# FabScan-Shield_v10.net
KiCad netlist of a schematic drawn in EAGLE
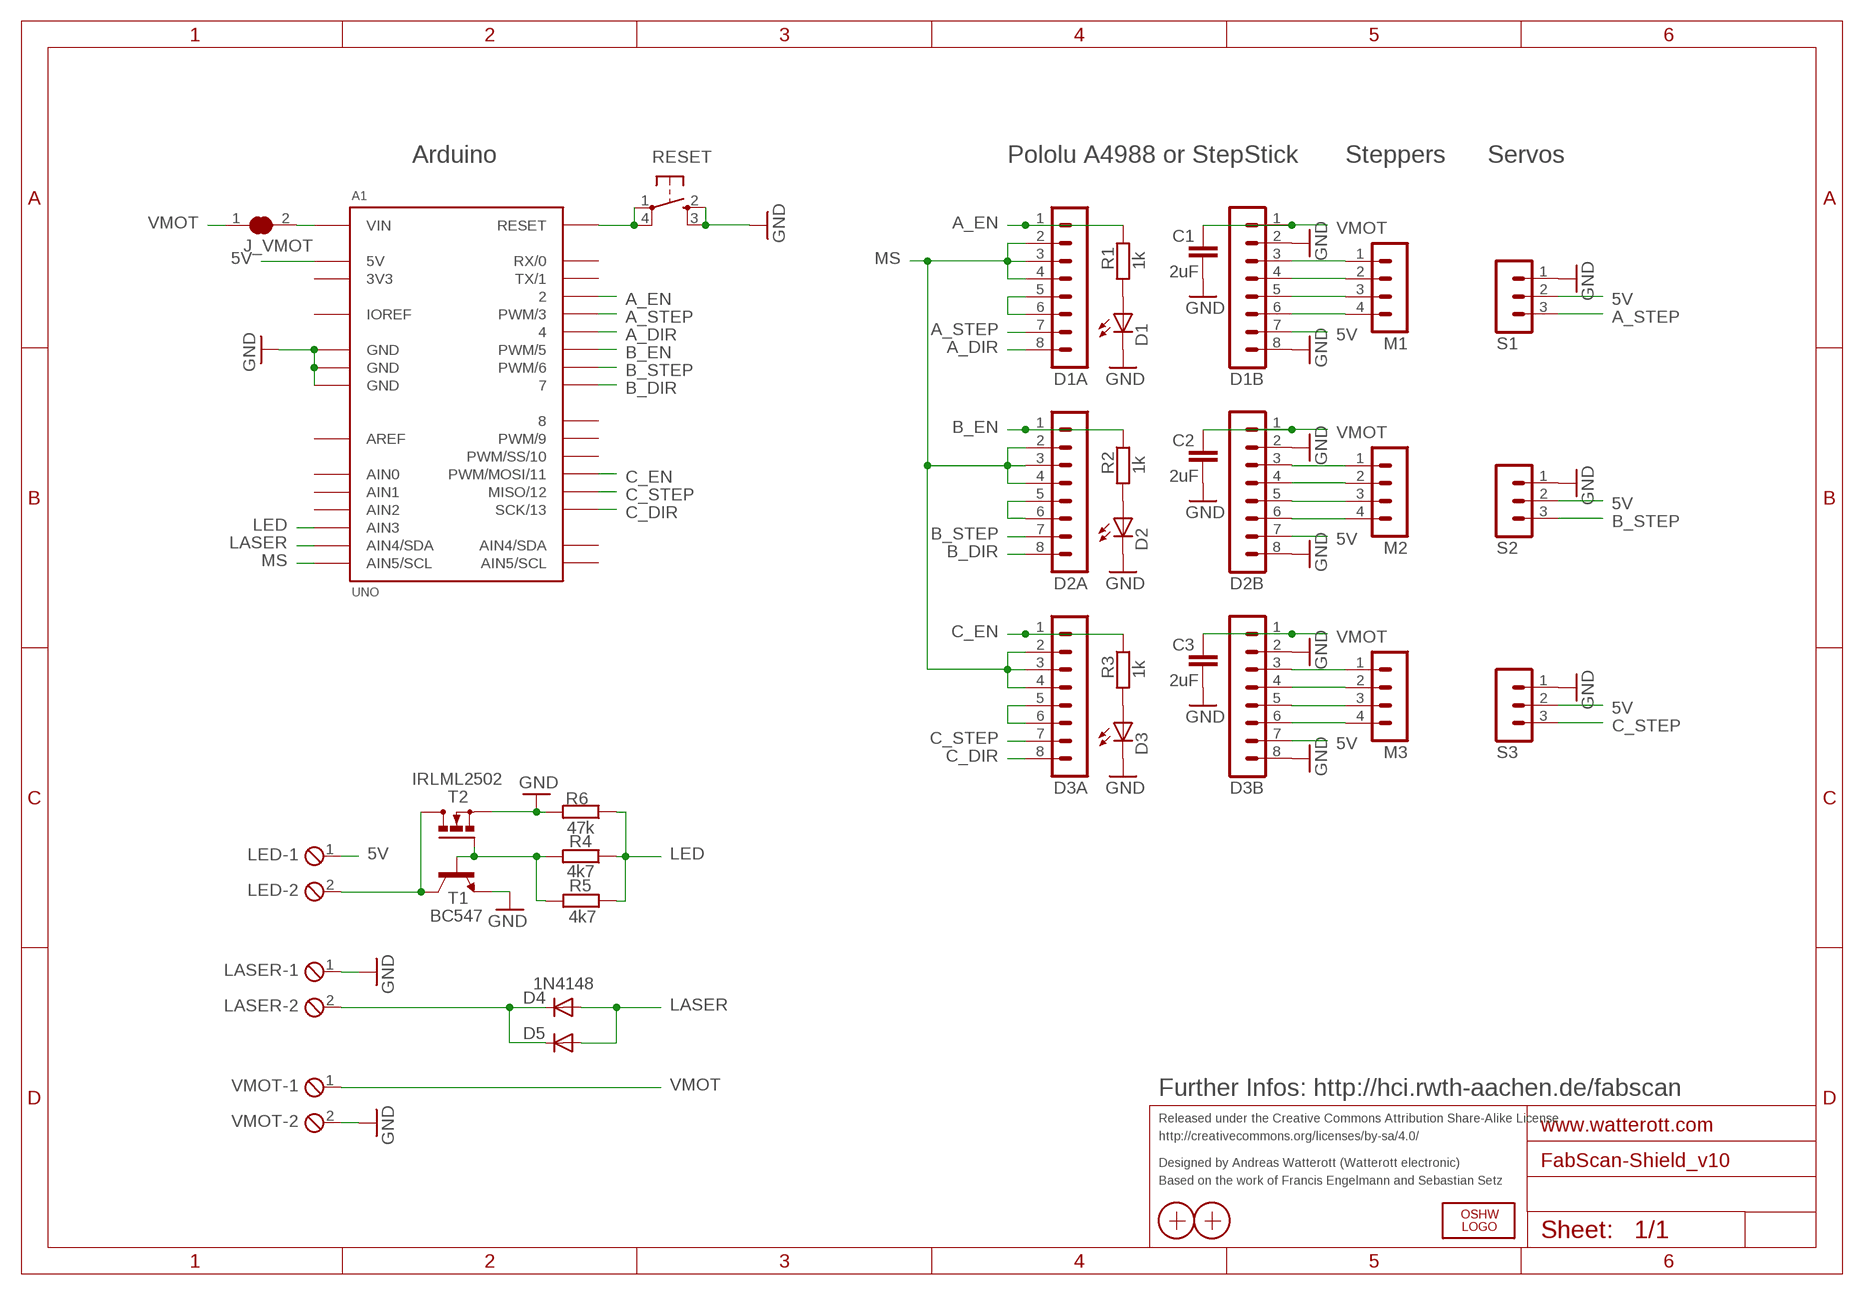
[diagram p0: schematic, sheet 1]

(export (version "E")
  (design (tool "Eeschema 10.0.6"))
  (components
    (comp (ref "A1")
      (value "UNO")
      (footprint "eagle-import:UNO")
      (libsource (lib "eagle-import") (part "UNO"))
    )
    (comp (ref "C1")
      (value "2uF")
      (footprint "eagle-import:C0603")
      (libsource (lib "eagle-import") (part "C-EUC0603"))
    )
    (comp (ref "C2")
      (value "2uF")
      (footprint "eagle-import:C0603")
      (libsource (lib "eagle-import") (part "C-EUC0603"))
    )
    (comp (ref "C3")
      (value "2uF")
      (footprint "eagle-import:C0603")
      (libsource (lib "eagle-import") (part "C-EUC0603"))
    )
    (comp (ref "D1")
      (value "LEDCHIPLED_0603")
      (footprint "eagle-import:CHIPLED_0603")
      (libsource (lib "eagle-import") (part "LEDCHIPLED_0603"))
    )
    (comp (ref "D1A")
      (value "MA08-1")
      (footprint "eagle-import:MA08-1")
      (libsource (lib "eagle-import") (part "MA08-1"))
    )
    (comp (ref "D1B")
      (value "MA08-1")
      (footprint "eagle-import:MA08-1")
      (libsource (lib "eagle-import") (part "MA08-1"))
    )
    (comp (ref "D2")
      (value "LEDCHIPLED_0603")
      (footprint "eagle-import:CHIPLED_0603")
      (libsource (lib "eagle-import") (part "LEDCHIPLED_0603"))
    )
    (comp (ref "D2A")
      (value "MA08-1")
      (footprint "eagle-import:MA08-1")
      (libsource (lib "eagle-import") (part "MA08-1"))
    )
    (comp (ref "D2B")
      (value "MA08-1")
      (footprint "eagle-import:MA08-1")
      (libsource (lib "eagle-import") (part "MA08-1"))
    )
    (comp (ref "D3")
      (value "LEDCHIPLED_0603")
      (footprint "eagle-import:CHIPLED_0603")
      (libsource (lib "eagle-import") (part "LEDCHIPLED_0603"))
    )
    (comp (ref "D3A")
      (value "MA08-1")
      (footprint "eagle-import:MA08-1")
      (libsource (lib "eagle-import") (part "MA08-1"))
    )
    (comp (ref "D3B")
      (value "MA08-1")
      (footprint "eagle-import:MA08-1")
      (libsource (lib "eagle-import") (part "MA08-1"))
    )
    (comp (ref "D4")
      (value "1N4148")
      (footprint "eagle-import:DO35-7")
      (libsource (lib "eagle-import") (part "1N4148DO35-7"))
    )
    (comp (ref "D5")
      (value "DIODE-SOD106-R")
      (footprint "eagle-import:SOD106-R")
      (libsource (lib "eagle-import") (part "DIODE-SOD106-R"))
    )
    (comp (ref "J_VMOT")
      (value "SJ")
      (footprint "eagle-import:SJ")
      (libsource (lib "eagle-import") (part "SJ"))
    )
    (comp (ref "LASER")
      (value "MPT2")
      (footprint "eagle-import:2POL254")
      (fields (field (name "OC_FARNELL") "unknown") (field (name "OC_NEWARK") "unknown"))
      (libsource (lib "eagle-import") (part "MPT2"))
    )
    (comp (ref "LED")
      (value "MPT2")
      (footprint "eagle-import:2POL254")
      (libsource (lib "eagle-import") (part "MPT2"))
    )
    (comp (ref "LOGO2")
      (value "OSHW_LOGO_6MILX0100-NT")
      (footprint "eagle-import:OSHW_6X100_NOTEXT")
      (libsource (lib "eagle-import") (part "OSHW_LOGO_6MILX0100-NT"))
    )
    (comp (ref "M1")
      (value "MA04-1")
      (footprint "eagle-import:MA04-1")
      (libsource (lib "eagle-import") (part "MA04-1"))
    )
    (comp (ref "M2")
      (value "MA04-1")
      (footprint "eagle-import:MA04-1")
      (fields (field (name "OC_FARNELL") "unknown") (field (name "OC_NEWARK") "unknown"))
      (libsource (lib "eagle-import") (part "MA04-1"))
    )
    (comp (ref "M3")
      (value "MA04-1")
      (footprint "eagle-import:MA04-1")
      (fields (field (name "OC_FARNELL") "unknown") (field (name "OC_NEWARK") "unknown"))
      (libsource (lib "eagle-import") (part "MA04-1"))
    )
    (comp (ref "R1")
      (value "1k")
      (footprint "eagle-import:R0603")
      (libsource (lib "eagle-import") (part "R-EU_R0603"))
    )
    (comp (ref "R2")
      (value "1k")
      (footprint "eagle-import:R0603")
      (libsource (lib "eagle-import") (part "R-EU_R0603"))
    )
    (comp (ref "R3")
      (value "1k")
      (footprint "eagle-import:R0603")
      (libsource (lib "eagle-import") (part "R-EU_R0603"))
    )
    (comp (ref "R4")
      (value "4k7")
      (footprint "eagle-import:0204_7")
      (libsource (lib "eagle-import") (part "R-EU_0204/7"))
    )
    (comp (ref "R5")
      (value "4k7")
      (footprint "eagle-import:R0603")
      (libsource (lib "eagle-import") (part "R-EU_R0603"))
    )
    (comp (ref "R6")
      (value "47k")
      (footprint "eagle-import:R0603")
      (libsource (lib "eagle-import") (part "R-EU_R0603"))
    )
    (comp (ref "RESET")
      (value "SW_SMDS")
      (footprint "eagle-import:SW_SMD4")
      (libsource (lib "eagle-import") (part "SW_SMDS"))
    )
    (comp (ref "S1")
      (value "MA03-1")
      (footprint "eagle-import:MA03-1")
      (libsource (lib "eagle-import") (part "MA03-1"))
    )
    (comp (ref "S2")
      (value "MA03-1")
      (footprint "eagle-import:MA03-1")
      (libsource (lib "eagle-import") (part "MA03-1"))
    )
    (comp (ref "S3")
      (value "MA03-1")
      (footprint "eagle-import:MA03-1")
      (libsource (lib "eagle-import") (part "MA03-1"))
    )
    (comp (ref "T1")
      (value "BC547")
      (footprint "eagle-import:TO92")
      (libsource (lib "eagle-import") (part "BC547"))
    )
    (comp (ref "T2")
      (value "IRLML2502")
      (footprint "eagle-import:MICRO3")
      (libsource (lib "eagle-import") (part "IRLML2502"))
    )
    (comp (ref "VMOT")
      (value "MPT2")
      (footprint "eagle-import:2POL254")
      (fields (field (name "OC_FARNELL") "unknown") (field (name "OC_NEWARK") "unknown"))
      (libsource (lib "eagle-import") (part "MPT2"))
    )
    (comp (ref "X1")
      (value "PASSER")
      (footprint "eagle-import:PASSER")
      (libsource (lib "eagle-import") (part "PASSER"))
    )
    (comp (ref "X2")
      (value "PASSER")
      (footprint "eagle-import:PASSER")
      (libsource (lib "eagle-import") (part "PASSER"))
    )
  )
  (nets
    (net (code "1") (name "/3V3") (class "Default")
      (node (ref "A1") (pin "3V3") (pinfunction "3V3_3V3") (pintype "power_in"))
    )
    (net (code "2") (name "/5V") (class "Default")
      (node (ref "A1") (pin "5V") (pinfunction "5V_5V") (pintype "power_in"))
      (node (ref "D1B") (pin "7") (pinfunction "7_7") (pintype "passive"))
      (node (ref "D2B") (pin "7") (pinfunction "7_7") (pintype "passive"))
      (node (ref "D3B") (pin "7") (pinfunction "7_7") (pintype "passive"))
      (node (ref "LED") (pin "1") (pinfunction "1_1") (pintype "passive"))
      (node (ref "S1") (pin "2") (pinfunction "2_2") (pintype "passive"))
      (node (ref "S2") (pin "2") (pinfunction "2_2") (pintype "passive"))
      (node (ref "S3") (pin "2") (pinfunction "2_2") (pintype "passive"))
    )
    (net (code "3") (name "/AREF") (class "Default")
      (node (ref "A1") (pin "AREF") (pinfunction "AREF_AREF") (pintype "power_in"))
    )
    (net (code "4") (name "/A_DIR") (class "Default")
      (node (ref "A1") (pin "4") (pinfunction "4_4") (pintype "bidirectional"))
      (node (ref "D1A") (pin "8") (pinfunction "8_8") (pintype "passive"))
    )
    (net (code "5") (name "/A_EN") (class "Default")
      (node (ref "A1") (pin "2") (pinfunction "2_2") (pintype "bidirectional"))
      (node (ref "D1A") (pin "1") (pinfunction "1_1") (pintype "passive"))
      (node (ref "R1") (pin "1") (pinfunction "1_1") (pintype "passive"))
    )
    (net (code "6") (name "/A_STEP") (class "Default")
      (node (ref "A1") (pin "3") (pinfunction "PWM/3_3") (pintype "bidirectional"))
      (node (ref "D1A") (pin "7") (pinfunction "7_7") (pintype "passive"))
      (node (ref "S1") (pin "3") (pinfunction "3_3") (pintype "passive"))
    )
    (net (code "7") (name "/B_DIR") (class "Default")
      (node (ref "A1") (pin "7") (pinfunction "7_7") (pintype "bidirectional"))
      (node (ref "D2A") (pin "8") (pinfunction "8_8") (pintype "passive"))
    )
    (net (code "8") (name "/B_EN") (class "Default")
      (node (ref "A1") (pin "5") (pinfunction "PWM/5_5") (pintype "bidirectional"))
      (node (ref "D2A") (pin "1") (pinfunction "1_1") (pintype "passive"))
      (node (ref "R2") (pin "1") (pinfunction "1_1") (pintype "passive"))
    )
    (net (code "9") (name "/B_STEP") (class "Default")
      (node (ref "A1") (pin "6") (pinfunction "PWM/6_6") (pintype "bidirectional"))
      (node (ref "D2A") (pin "7") (pinfunction "7_7") (pintype "passive"))
      (node (ref "S2") (pin "3") (pinfunction "3_3") (pintype "passive"))
    )
    (net (code "10") (name "/C_DIR") (class "Default")
      (node (ref "A1") (pin "13") (pinfunction "SCK/13_13") (pintype "bidirectional"))
      (node (ref "D3A") (pin "8") (pinfunction "8_8") (pintype "passive"))
    )
    (net (code "11") (name "/C_EN") (class "Default")
      (node (ref "A1") (pin "11") (pinfunction "PWM/MOSI/11_11") (pintype "bidirectional"))
      (node (ref "D3A") (pin "1") (pinfunction "1_1") (pintype "passive"))
      (node (ref "R3") (pin "1") (pinfunction "1_1") (pintype "passive"))
    )
    (net (code "12") (name "/C_STEP") (class "Default")
      (node (ref "A1") (pin "12") (pinfunction "MISO/12_12") (pintype "bidirectional"))
      (node (ref "D3A") (pin "7") (pinfunction "7_7") (pintype "passive"))
      (node (ref "S3") (pin "3") (pinfunction "3_3") (pintype "passive"))
    )
    (net (code "13") (name "/IOREF") (class "Default")
      (node (ref "A1") (pin "IOREF") (pinfunction "IOREF_IOREF") (pintype "power_in"))
    )
    (net (code "14") (name "/LASER") (class "Default")
      (node (ref "A1") (pin "AIN4") (pinfunction "AIN4/SDA_AIN4") (pintype "bidirectional"))
      (node (ref "D4") (pin "A") (pinfunction "A_A") (pintype "passive"))
      (node (ref "D5") (pin "A") (pinfunction "A_A") (pintype "passive"))
    )
    (net (code "15") (name "/LED") (class "Default")
      (node (ref "A1") (pin "AIN3") (pinfunction "AIN3_AIN3") (pintype "bidirectional"))
      (node (ref "R4") (pin "1") (pinfunction "1_1") (pintype "passive"))
      (node (ref "R5") (pin "2") (pinfunction "2_2") (pintype "passive"))
      (node (ref "R6") (pin "1") (pinfunction "1_1") (pintype "passive"))
    )
    (net (code "16") (name "/MS") (class "Default")
      (node (ref "A1") (pin "AIN5") (pinfunction "AIN5/SCL_AIN5") (pintype "bidirectional"))
      (node (ref "D1A") (pin "2") (pinfunction "2_2") (pintype "passive"))
      (node (ref "D1A") (pin "3") (pinfunction "3_3") (pintype "passive"))
      (node (ref "D1A") (pin "4") (pinfunction "4_4") (pintype "passive"))
      (node (ref "D2A") (pin "2") (pinfunction "2_2") (pintype "passive"))
      (node (ref "D2A") (pin "3") (pinfunction "3_3") (pintype "passive"))
      (node (ref "D2A") (pin "4") (pinfunction "4_4") (pintype "passive"))
      (node (ref "D3A") (pin "2") (pinfunction "2_2") (pintype "passive"))
      (node (ref "D3A") (pin "3") (pinfunction "3_3") (pintype "passive"))
      (node (ref "D3A") (pin "4") (pinfunction "4_4") (pintype "passive"))
    )
    (net (code "17") (name "/VMOT") (class "Default")
      (node (ref "C1") (pin "1") (pinfunction "1_1") (pintype "passive"))
      (node (ref "C2") (pin "1") (pinfunction "1_1") (pintype "passive"))
      (node (ref "C3") (pin "1") (pinfunction "1_1") (pintype "passive"))
      (node (ref "D1B") (pin "1") (pinfunction "1_1") (pintype "passive"))
      (node (ref "D2B") (pin "1") (pinfunction "1_1") (pintype "passive"))
      (node (ref "D3B") (pin "1") (pinfunction "1_1") (pintype "passive"))
      (node (ref "J_VMOT") (pin "1") (pinfunction "1_1") (pintype "passive"))
      (node (ref "VMOT") (pin "1") (pinfunction "1_1") (pintype "passive"))
    )
    (net (code "18") (name "GND") (class "Default")
      (node (ref "A1") (pin "GND@1") (pinfunction "GND_GND@1") (pintype "power_in"))
      (node (ref "A1") (pin "GND@2") (pinfunction "GND_GND@2") (pintype "power_in"))
      (node (ref "A1") (pin "GND@3") (pinfunction "GND_GND@3") (pintype "power_in"))
      (node (ref "C1") (pin "2") (pinfunction "2_2") (pintype "passive"))
      (node (ref "C2") (pin "2") (pinfunction "2_2") (pintype "passive"))
      (node (ref "C3") (pin "2") (pinfunction "2_2") (pintype "passive"))
      (node (ref "D1") (pin "C") (pinfunction "C_C") (pintype "passive"))
      (node (ref "D1B") (pin "2") (pinfunction "2_2") (pintype "passive"))
      (node (ref "D1B") (pin "8") (pinfunction "8_8") (pintype "passive"))
      (node (ref "D2") (pin "C") (pinfunction "C_C") (pintype "passive"))
      (node (ref "D2B") (pin "2") (pinfunction "2_2") (pintype "passive"))
      (node (ref "D2B") (pin "8") (pinfunction "8_8") (pintype "passive"))
      (node (ref "D3") (pin "C") (pinfunction "C_C") (pintype "passive"))
      (node (ref "D3B") (pin "2") (pinfunction "2_2") (pintype "passive"))
      (node (ref "D3B") (pin "8") (pinfunction "8_8") (pintype "passive"))
      (node (ref "LASER") (pin "1") (pinfunction "1_1") (pintype "passive"))
      (node (ref "R6") (pin "2") (pinfunction "2_2") (pintype "passive"))
      (node (ref "RESET") (pin "2") (pinfunction "S_2") (pintype "passive"))
      (node (ref "RESET") (pin "3") (pinfunction "S1_3") (pintype "passive"))
      (node (ref "S1") (pin "1") (pinfunction "1_1") (pintype "passive"))
      (node (ref "S2") (pin "1") (pinfunction "1_1") (pintype "passive"))
      (node (ref "S3") (pin "1") (pinfunction "1_1") (pintype "passive"))
      (node (ref "T1") (pin "1") (pinfunction "E_1") (pintype "passive"))
      (node (ref "T2") (pin "2") (pinfunction "S_2") (pintype "passive"))
      (node (ref "VMOT") (pin "2") (pinfunction "1_2") (pintype "passive"))
    )
    (net (code "19") (name "Net-(A1-PadVIN)") (class "Default")
      (node (ref "A1") (pin "VIN") (pinfunction "VIN_VIN") (pintype "power_in"))
      (node (ref "J_VMOT") (pin "2") (pinfunction "2_2") (pintype "passive"))
    )
    (net (code "20") (name "Net-(A1-RESET)") (class "Default")
      (node (ref "A1") (pin "RST") (pinfunction "RESET_RST") (pintype "bidirectional"))
      (node (ref "RESET") (pin "1") (pinfunction "P_1") (pintype "passive"))
      (node (ref "RESET") (pin "4") (pinfunction "P1_4") (pintype "passive"))
    )
    (net (code "21") (name "Net-(D1-PadA)") (class "Default")
      (node (ref "D1") (pin "A") (pinfunction "A_A") (pintype "passive"))
      (node (ref "R1") (pin "2") (pinfunction "2_2") (pintype "passive"))
    )
    (net (code "22") (name "Net-(D1A-Pad5)") (class "Default")
      (node (ref "D1A") (pin "5") (pinfunction "5_5") (pintype "passive"))
      (node (ref "D1A") (pin "6") (pinfunction "6_6") (pintype "passive"))
    )
    (net (code "23") (name "Net-(D1B-Pad3)") (class "Default")
      (node (ref "D1B") (pin "3") (pinfunction "3_3") (pintype "passive"))
      (node (ref "M1") (pin "1") (pinfunction "1_1") (pintype "passive"))
    )
    (net (code "24") (name "Net-(D1B-Pad4)") (class "Default")
      (node (ref "D1B") (pin "4") (pinfunction "4_4") (pintype "passive"))
      (node (ref "M1") (pin "2") (pinfunction "2_2") (pintype "passive"))
    )
    (net (code "25") (name "Net-(D1B-Pad5)") (class "Default")
      (node (ref "D1B") (pin "5") (pinfunction "5_5") (pintype "passive"))
      (node (ref "M1") (pin "3") (pinfunction "3_3") (pintype "passive"))
    )
    (net (code "26") (name "Net-(D1B-Pad6)") (class "Default")
      (node (ref "D1B") (pin "6") (pinfunction "6_6") (pintype "passive"))
      (node (ref "M1") (pin "4") (pinfunction "4_4") (pintype "passive"))
    )
    (net (code "27") (name "Net-(D2-PadA)") (class "Default")
      (node (ref "D2") (pin "A") (pinfunction "A_A") (pintype "passive"))
      (node (ref "R2") (pin "2") (pinfunction "2_2") (pintype "passive"))
    )
    (net (code "28") (name "Net-(D2A-Pad5)") (class "Default")
      (node (ref "D2A") (pin "5") (pinfunction "5_5") (pintype "passive"))
      (node (ref "D2A") (pin "6") (pinfunction "6_6") (pintype "passive"))
    )
    (net (code "29") (name "Net-(D2B-Pad3)") (class "Default")
      (node (ref "D2B") (pin "3") (pinfunction "3_3") (pintype "passive"))
      (node (ref "M2") (pin "1") (pinfunction "1_1") (pintype "passive"))
    )
    (net (code "30") (name "Net-(D2B-Pad4)") (class "Default")
      (node (ref "D2B") (pin "4") (pinfunction "4_4") (pintype "passive"))
      (node (ref "M2") (pin "2") (pinfunction "2_2") (pintype "passive"))
    )
    (net (code "31") (name "Net-(D2B-Pad5)") (class "Default")
      (node (ref "D2B") (pin "5") (pinfunction "5_5") (pintype "passive"))
      (node (ref "M2") (pin "3") (pinfunction "3_3") (pintype "passive"))
    )
    (net (code "32") (name "Net-(D2B-Pad6)") (class "Default")
      (node (ref "D2B") (pin "6") (pinfunction "6_6") (pintype "passive"))
      (node (ref "M2") (pin "4") (pinfunction "4_4") (pintype "passive"))
    )
    (net (code "33") (name "Net-(D3-PadA)") (class "Default")
      (node (ref "D3") (pin "A") (pinfunction "A_A") (pintype "passive"))
      (node (ref "R3") (pin "2") (pinfunction "2_2") (pintype "passive"))
    )
    (net (code "34") (name "Net-(D3A-Pad5)") (class "Default")
      (node (ref "D3A") (pin "5") (pinfunction "5_5") (pintype "passive"))
      (node (ref "D3A") (pin "6") (pinfunction "6_6") (pintype "passive"))
    )
    (net (code "35") (name "Net-(D3B-Pad3)") (class "Default")
      (node (ref "D3B") (pin "3") (pinfunction "3_3") (pintype "passive"))
      (node (ref "M3") (pin "1") (pinfunction "1_1") (pintype "passive"))
    )
    (net (code "36") (name "Net-(D3B-Pad4)") (class "Default")
      (node (ref "D3B") (pin "4") (pinfunction "4_4") (pintype "passive"))
      (node (ref "M3") (pin "2") (pinfunction "2_2") (pintype "passive"))
    )
    (net (code "37") (name "Net-(D3B-Pad5)") (class "Default")
      (node (ref "D3B") (pin "5") (pinfunction "5_5") (pintype "passive"))
      (node (ref "M3") (pin "3") (pinfunction "3_3") (pintype "passive"))
    )
    (net (code "38") (name "Net-(D3B-Pad6)") (class "Default")
      (node (ref "D3B") (pin "6") (pinfunction "6_6") (pintype "passive"))
      (node (ref "M3") (pin "4") (pinfunction "4_4") (pintype "passive"))
    )
    (net (code "39") (name "Net-(LASERB-1)") (class "Default")
      (node (ref "D4") (pin "C") (pinfunction "C_C") (pintype "passive"))
      (node (ref "D5") (pin "C") (pinfunction "C_C") (pintype "passive"))
      (node (ref "LASER") (pin "2") (pinfunction "1_2") (pintype "passive"))
    )
    (net (code "40") (name "Net-(LEDB-1)") (class "Default")
      (node (ref "LED") (pin "2") (pinfunction "1_2") (pintype "passive"))
      (node (ref "T1") (pin "3") (pinfunction "C_3") (pintype "passive"))
      (node (ref "T2") (pin "3") (pinfunction "D_3") (pintype "passive"))
    )
    (net (code "41") (name "Net-(T1-B)") (class "Default")
      (node (ref "R4") (pin "2") (pinfunction "2_2") (pintype "passive"))
      (node (ref "R5") (pin "1") (pinfunction "1_1") (pintype "passive"))
      (node (ref "T1") (pin "2") (pinfunction "B_2") (pintype "passive"))
      (node (ref "T2") (pin "1") (pinfunction "G_1") (pintype "passive"))
    )
    (net (code "42") (name "unconnected-(A1-AIN4{slash}SDA-PadSDA)") (class "Default")
      (node (ref "A1") (pin "SDA") (pinfunction "AIN4/SDA_SDA") (pintype "bidirectional"))
    )
    (net (code "43") (name "unconnected-(A1-AIN5{slash}SCL-PadSCL)") (class "Default")
      (node (ref "A1") (pin "SCL") (pinfunction "AIN5/SCL_SCL") (pintype "bidirectional"))
    )
    (net (code "44") (name "unconnected-(A1-PWM{slash}9-Pad9)") (class "Default")
      (node (ref "A1") (pin "9") (pinfunction "PWM/9_9") (pintype "bidirectional"))
    )
    (net (code "45") (name "unconnected-(A1-PWM{slash}SS{slash}10-Pad10)") (class "Default")
      (node (ref "A1") (pin "10") (pinfunction "PWM/SS/10_10") (pintype "bidirectional"))
    )
    (net (code "46") (name "unconnected-(A1-Pad8)") (class "Default")
      (node (ref "A1") (pin "8") (pinfunction "8_8") (pintype "bidirectional"))
    )
    (net (code "47") (name "unconnected-(A1-PadAIN0)") (class "Default")
      (node (ref "A1") (pin "AIN0") (pinfunction "AIN0_AIN0") (pintype "bidirectional"))
    )
    (net (code "48") (name "unconnected-(A1-PadAIN1)") (class "Default")
      (node (ref "A1") (pin "AIN1") (pinfunction "AIN1_AIN1") (pintype "bidirectional"))
    )
    (net (code "49") (name "unconnected-(A1-PadAIN2)") (class "Default")
      (node (ref "A1") (pin "AIN2") (pinfunction "AIN2_AIN2") (pintype "bidirectional"))
    )
    (net (code "50") (name "unconnected-(A1-RX{slash}0-Pad0)") (class "Default")
      (node (ref "A1") (pin "0") (pinfunction "RX/0_0") (pintype "bidirectional"))
    )
    (net (code "51") (name "unconnected-(A1-TX{slash}1-Pad1)") (class "Default")
      (node (ref "A1") (pin "1") (pinfunction "TX/1_1") (pintype "bidirectional"))
    )
  )
)
